# cerebro5_4.net
KiCad netlist of a schematic drawn in EAGLE
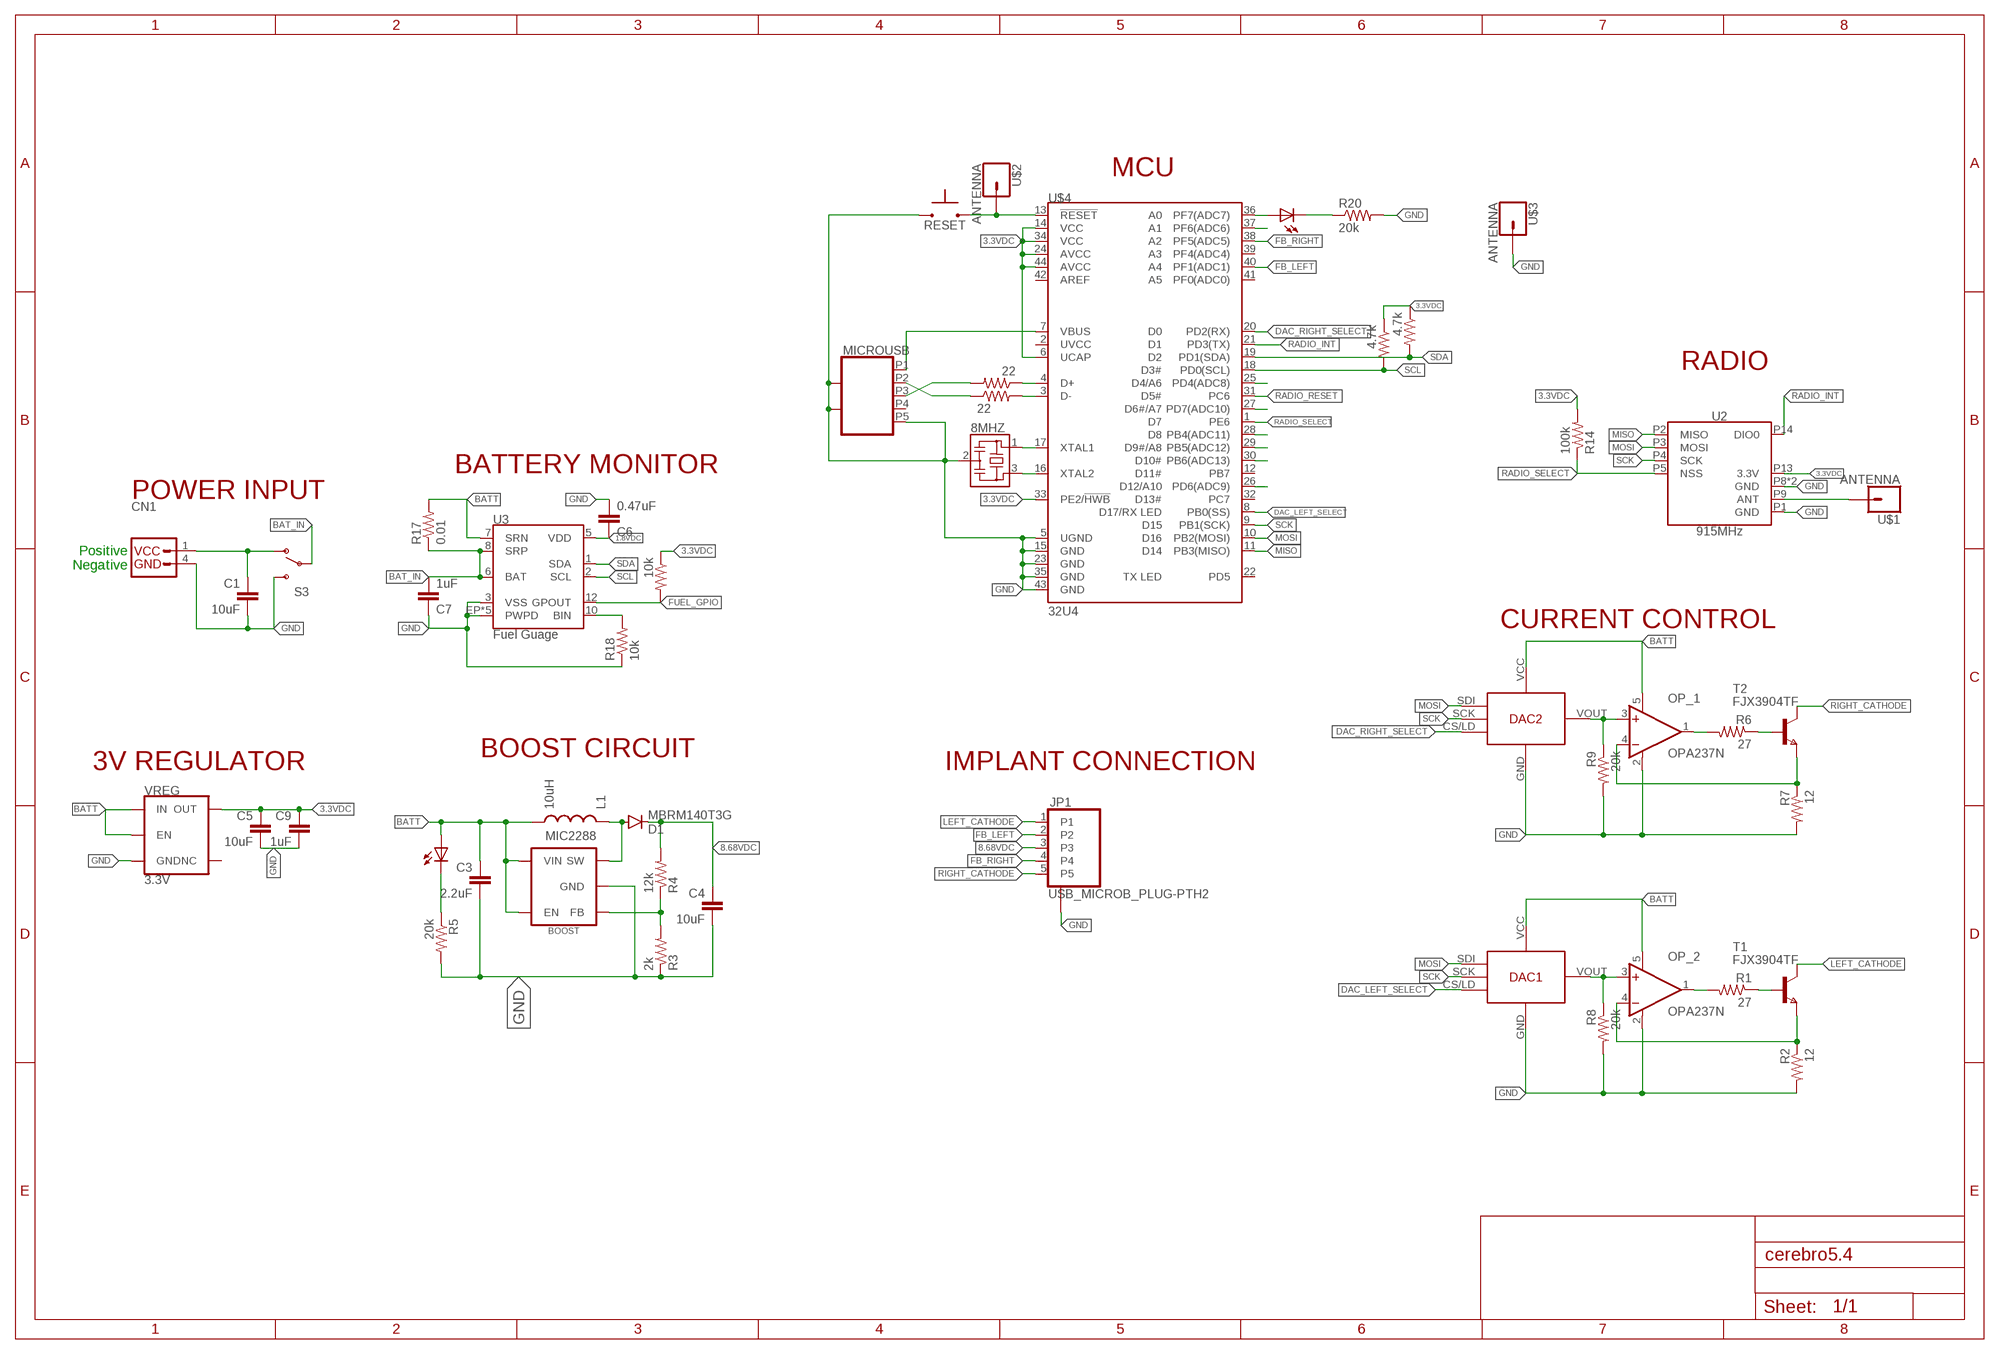
[diagram p0: schematic, sheet 1]

(export (version "E")
  (design (tool "Eeschema 10.0.6"))
  (components
    (comp (ref "8MHZ")
      (value "RESONATOR_CSTCE_V")
      (footprint "eagle-import:CSTCE_V")
      (libsource (lib "eagle-import") (part "RESONATOR_CSTCE_V"))
    )
    (comp (ref "C1")
      (value "10uF")
      (footprint "eagle-import:0805")
      (libsource (lib "eagle-import") (part "10UF-0805-10V-10%"))
    )
    (comp (ref "C3")
      (value "2.2uF")
      (footprint "eagle-import:0805")
      (libsource (lib "eagle-import") (part "2.2UF-0805-25V-(+80/-20%)"))
    )
    (comp (ref "C4")
      (value "10uF")
      (footprint "eagle-import:0805")
      (libsource (lib "eagle-import") (part "10UF-0805-10V-10%"))
    )
    (comp (ref "C5")
      (value "10uF")
      (footprint "eagle-import:0805")
      (libsource (lib "eagle-import") (part "10UF-0805-10V-10%"))
    )
    (comp (ref "C6")
      (value "0.47uF")
      (footprint "eagle-import:0805")
      (libsource (lib "eagle-import") (part "10UF-0805-10V-10%"))
    )
    (comp (ref "C7")
      (value "1uF")
      (footprint "eagle-import:0805")
      (libsource (lib "eagle-import") (part "10UF-0805-10V-10%"))
    )
    (comp (ref "C9")
      (value "1uF")
      (footprint "eagle-import:0805")
      (libsource (lib "eagle-import") (part "10UF-0805-10V-10%"))
    )
    (comp (ref "CN1")
      (value "JST-SRJS-1MM")
      (footprint "eagle-import:1X04_1MM_RA")
      (libsource (lib "eagle-import") (part "JST-SRJS-1MM"))
    )
    (comp (ref "D1")
      (value "MBRM140T3G")
      (footprint "eagle-import:POWERMITE")
      (libsource (lib "eagle-import") (part "DIODEPOWERMITE"))
    )
    (comp (ref "DAC1")
      (value "DAC_LTC2630")
      (footprint "eagle-import:SC-70")
      (libsource (lib "eagle-import") (part "DAC_LTC2630"))
    )
    (comp (ref "DAC2")
      (value "DAC_LTC2630")
      (footprint "eagle-import:SC-70")
      (libsource (lib "eagle-import") (part "DAC_LTC2630"))
    )
    (comp (ref "INDICATOR_LED")
      (value "RED")
      (footprint "eagle-import:CHIP-LED0603")
      (libsource (lib "eagle-import") (part "LEDCHIP-LED0603"))
    )
    (comp (ref "INDICATOR_LED1")
      (value "AMBER")
      (footprint "eagle-import:CHIP-LED0603")
      (libsource (lib "eagle-import") (part "LEDCHIP-LED0603"))
    )
    (comp (ref "JP1")
      (value "USB_MICROB_PLUG-PTH2")
      (footprint "eagle-import:MICRO-B-TH")
      (libsource (lib "eagle-import") (part "USB_MICROB_PLUG-PTH2"))
    )
    (comp (ref "L1")
      (value "10uH")
      (footprint "eagle-import:1812")
      (libsource (lib "eagle-import") (part "INDUCTORLQH4"))
    )
    (comp (ref "MIC2288")
      (value "BOOST")
      (footprint "eagle-import:SOT23-5")
      (libsource (lib "eagle-import") (part "BOOST_CONVERTER"))
    )
    (comp (ref "MICROUSB")
      (value "USB_MICRO_SOCKET_HORZ_REINFORCED")
      (footprint "eagle-import:USB_HORZ_REINFORCED_MICRO")
      (libsource (lib "eagle-import") (part "USB_MICRO_SOCKET_HORZ_REINFORCED"))
    )
    (comp (ref "OP_1")
      (value "OPA237N")
      (footprint "eagle-import:SOT23-5")
      (fields (field (name "MF") "TEXAS INSTRUMENTS") (field (name "MPN") "OPA237NA/250"))
      (libsource (lib "eagle-import") (part "OPA237N"))
    )
    (comp (ref "OP_2")
      (value "OPA237N")
      (footprint "eagle-import:SOT23-5")
      (fields (field (name "MF") "TEXAS INSTRUMENTS") (field (name "MPN") "OPA237NA/250"))
      (libsource (lib "eagle-import") (part "OPA237N"))
    )
    (comp (ref "R1")
      (value "27")
      (footprint "eagle-import:0603-RES")
      (libsource (lib "eagle-import") (part "RESISTOR0603-RES"))
    )
    (comp (ref "R2")
      (value "12")
      (footprint "eagle-import:0603-RES")
      (libsource (lib "eagle-import") (part "RESISTOR0603-RES"))
    )
    (comp (ref "R3")
      (value "2k")
      (footprint "eagle-import:0603-RES")
      (libsource (lib "eagle-import") (part "RESISTOR0603-RES"))
    )
    (comp (ref "R4")
      (value "12k")
      (footprint "eagle-import:0805")
      (libsource (lib "eagle-import") (part "RESISTOR0805-RES"))
    )
    (comp (ref "R5")
      (value "20k")
      (footprint "eagle-import:0603-RES")
      (libsource (lib "eagle-import") (part "RESISTOR0603-RES"))
    )
    (comp (ref "R6")
      (value "27")
      (footprint "eagle-import:0603-RES")
      (libsource (lib "eagle-import") (part "RESISTOR0603-RES"))
    )
    (comp (ref "R7")
      (value "12")
      (footprint "eagle-import:0603-RES")
      (libsource (lib "eagle-import") (part "RESISTOR0603-RES"))
    )
    (comp (ref "R8")
      (value "20k")
      (footprint "eagle-import:0603-RES")
      (libsource (lib "eagle-import") (part "RESISTOR0603-RES"))
    )
    (comp (ref "R9")
      (value "20k")
      (footprint "eagle-import:0603-RES")
      (libsource (lib "eagle-import") (part "RESISTOR0603-RES"))
    )
    (comp (ref "R12")
      (value "22")
      (footprint "eagle-import:0603-RES")
      (libsource (lib "eagle-import") (part "RESISTOR0603-RES"))
    )
    (comp (ref "R13")
      (value "22")
      (footprint "eagle-import:0603-RES")
      (libsource (lib "eagle-import") (part "RESISTOR0603-RES"))
    )
    (comp (ref "R14")
      (value "100k")
      (footprint "eagle-import:0603-RES")
      (libsource (lib "eagle-import") (part "RESISTOR0603-RES"))
    )
    (comp (ref "R15")
      (value "4.7k")
      (footprint "eagle-import:0603-RES")
      (libsource (lib "eagle-import") (part "RESISTOR0603-RES"))
    )
    (comp (ref "R16")
      (value "4.7k")
      (footprint "eagle-import:0603-RES")
      (libsource (lib "eagle-import") (part "RESISTOR0603-RES"))
    )
    (comp (ref "R17")
      (value "0.01")
      (footprint "eagle-import:1206")
      (libsource (lib "eagle-import") (part "RESISTOR1206"))
    )
    (comp (ref "R18")
      (value "10k")
      (footprint "eagle-import:0603-RES")
      (libsource (lib "eagle-import") (part "RESISTOR0603-RES"))
    )
    (comp (ref "R19")
      (value "10k")
      (footprint "eagle-import:0603-RES")
      (libsource (lib "eagle-import") (part "RESISTOR0603-RES"))
    )
    (comp (ref "R20")
      (value "20k")
      (footprint "eagle-import:0603-RES")
      (libsource (lib "eagle-import") (part "RESISTOR0603-RES"))
    )
    (comp (ref "RESET")
      (value "SWITCH-MOMENTARY-NO")
      (footprint "eagle-import:SWITCH_MOMENTARY_XS")
      (libsource (lib "eagle-import") (part "SWITCH-MOMENTARY-NO"))
    )
    (comp (ref "S3")
      (value "SWITCH-SPDTSMD2")
      (footprint "eagle-import:SWITCH-SPDT-SMD")
      (libsource (lib "eagle-import") (part "SWITCH-SPDTSMD2"))
    )
    (comp (ref "T1")
      (value "FJX3904TF")
      (footprint "eagle-import:SOT323")
      (fields (field (name "MPN") "DSS4160U-7"))
      (libsource (lib "eagle-import") (part "NPNSOT323"))
    )
    (comp (ref "T2")
      (value "FJX3904TF")
      (footprint "eagle-import:SOT323")
      (fields (field (name "MPN") "DSS4160U-7"))
      (libsource (lib "eagle-import") (part "NPNSOT323"))
    )
    (comp (ref "U$1")
      (value "ANTENNA")
      (footprint "eagle-import:1X01")
      (libsource (lib "eagle-import") (part "ANTENNA"))
    )
    (comp (ref "U$2")
      (value "ANTENNA")
      (footprint "eagle-import:1X01")
      (libsource (lib "eagle-import") (part "ANTENNA"))
    )
    (comp (ref "U$3")
      (value "ANTENNA")
      (footprint "eagle-import:1X01")
      (libsource (lib "eagle-import") (part "ANTENNA"))
    )
    (comp (ref "U$4")
      (value "32U4")
      (footprint "eagle-import:QFN-44-NOPAD")
      (libsource (lib "eagle-import") (part "ATMEGA32U4QFN2"))
    )
    (comp (ref "U2")
      (value "915MHz")
      (footprint "eagle-import:RFM69HCW-XXXS2")
      (libsource (lib "eagle-import") (part "RFM69HCW-915"))
    )
    (comp (ref "U3")
      (value "Fuel Guage")
      (footprint "eagle-import:PDSO-N12")
      (libsource (lib "eagle-import") (part "BQ27441-G1"))
    )
    (comp (ref "VREG")
      (value "3.3V")
      (footprint "eagle-import:SOT23-5")
      (libsource (lib "eagle-import") (part "V_REG_AP2112K-3.3V"))
    )
  )
  (nets
    (net (code "1") (name "1.8VDC") (class "Default")
      (node (ref "C6") (pin "1") (pinfunction "1_1") (pintype "passive"))
      (node (ref "U3") (pin "5") (pinfunction "VDD_5") (pintype "bidirectional"))
    )
    (net (code "2") (name "3.3VDC") (class "Default")
      (node (ref "C5") (pin "1") (pinfunction "1_1") (pintype "passive"))
      (node (ref "C9") (pin "1") (pinfunction "1_1") (pintype "passive"))
      (node (ref "R14") (pin "2") (pinfunction "2_2") (pintype "passive"))
      (node (ref "R15") (pin "1") (pinfunction "1_1") (pintype "passive"))
      (node (ref "R16") (pin "1") (pinfunction "1_1") (pintype "passive"))
      (node (ref "R19") (pin "1") (pinfunction "1_1") (pintype "passive"))
      (node (ref "U$4") (pin "14") (pinfunction "VCC_14") (pintype "bidirectional"))
      (node (ref "U$4") (pin "24") (pinfunction "AVCC_24") (pintype "bidirectional"))
      (node (ref "U$4") (pin "33") (pinfunction "PE2/~{HWB}_33") (pintype "bidirectional"))
      (node (ref "U$4") (pin "34") (pinfunction "VCC_34") (pintype "bidirectional"))
      (node (ref "U$4") (pin "44") (pinfunction "AVCC_44") (pintype "bidirectional"))
      (node (ref "U$4") (pin "6") (pinfunction "UCAP_6") (pintype "bidirectional"))
      (node (ref "U2") (pin "P13") (pinfunction "3.3V_P13") (pintype "power_in"))
      (node (ref "VREG") (pin "5") (pinfunction "OUT_5") (pintype "passive"))
    )
    (net (code "3") (name "8.68VDC") (class "Default")
      (node (ref "C4") (pin "1") (pinfunction "1_1") (pintype "passive"))
      (node (ref "D1") (pin "CATHODE") (pinfunction "C_CATHODE") (pintype "passive"))
      (node (ref "JP1") (pin "3") (pinfunction "P3_3") (pintype "bidirectional"))
      (node (ref "R4") (pin "2") (pinfunction "2_2") (pintype "passive"))
    )
    (net (code "4") (name "BATT") (class "Default")
      (node (ref "C3") (pin "1") (pinfunction "1_1") (pintype "passive"))
      (node (ref "DAC1") (pin "VCC") (pinfunction "VIN_VCC") (pintype "bidirectional"))
      (node (ref "DAC2") (pin "VCC") (pinfunction "VIN_VCC") (pintype "bidirectional"))
      (node (ref "INDICATOR_LED") (pin "A") (pinfunction "A_A") (pintype "passive"))
      (node (ref "L1") (pin "P$2") (pinfunction "2_P$2") (pintype "passive"))
      (node (ref "L1") (pin "P$4") (pinfunction "2_P$4") (pintype "passive"))
      (node (ref "MIC2288") (pin "4") (pinfunction "EN_4") (pintype "input"))
      (node (ref "MIC2288") (pin "5") (pinfunction "VIN_5") (pintype "passive"))
      (node (ref "OP_1") (pin "5") (pinfunction "V+_5") (pintype "power_in"))
      (node (ref "OP_2") (pin "5") (pinfunction "V+_5") (pintype "power_in"))
      (node (ref "R17") (pin "2") (pinfunction "2_2") (pintype "passive"))
      (node (ref "U3") (pin "7") (pinfunction "SRN_7") (pintype "bidirectional"))
      (node (ref "VREG") (pin "1") (pinfunction "IN_1") (pintype "input"))
      (node (ref "VREG") (pin "3") (pinfunction "EN_3") (pintype "input"))
    )
    (net (code "5") (name "BAT_IN") (class "Default")
      (node (ref "C7") (pin "2") (pinfunction "2_2") (pintype "passive"))
      (node (ref "R17") (pin "1") (pinfunction "1_1") (pintype "passive"))
      (node (ref "S3") (pin "2") (pinfunction "P_2") (pintype "passive"))
      (node (ref "U3") (pin "6") (pinfunction "BAT_6") (pintype "bidirectional"))
      (node (ref "U3") (pin "8") (pinfunction "SRP_8") (pintype "bidirectional"))
    )
    (net (code "6") (name "DAC_LEFT_SELECT") (class "Default")
      (node (ref "DAC1") (pin "CS/LD") (pinfunction "CS/LD_CS/LD") (pintype "bidirectional"))
      (node (ref "U$4") (pin "8") (pinfunction "PB0(SS)_8") (pintype "bidirectional"))
    )
    (net (code "7") (name "DAC_RIGHT_SELECT") (class "Default")
      (node (ref "DAC2") (pin "CS/LD") (pinfunction "CS/LD_CS/LD") (pintype "bidirectional"))
      (node (ref "U$4") (pin "20") (pinfunction "PD2(RX)_20") (pintype "bidirectional"))
    )
    (net (code "8") (name "FB_LEFT") (class "Default")
      (node (ref "JP1") (pin "2") (pinfunction "P2_2") (pintype "bidirectional"))
      (node (ref "U$4") (pin "40") (pinfunction "PF1(ADC1)_40") (pintype "bidirectional"))
    )
    (net (code "9") (name "FB_RIGHT") (class "Default")
      (node (ref "JP1") (pin "4") (pinfunction "P4_4") (pintype "bidirectional"))
      (node (ref "U$4") (pin "38") (pinfunction "PF5(ADC5)_38") (pintype "bidirectional"))
    )
    (net (code "10") (name "FUEL_GPIO") (class "Default")
      (node (ref "R19") (pin "2") (pinfunction "2_2") (pintype "passive"))
      (node (ref "U3") (pin "12") (pinfunction "GPOUT_12") (pintype "bidirectional"))
    )
    (net (code "11") (name "GND") (class "Default")
      (node (ref "8MHZ") (pin "2") (pinfunction "2_2") (pintype "passive"))
      (node (ref "C1") (pin "2") (pinfunction "2_2") (pintype "passive"))
      (node (ref "C3") (pin "2") (pinfunction "2_2") (pintype "passive"))
      (node (ref "C4") (pin "2") (pinfunction "2_2") (pintype "passive"))
      (node (ref "C5") (pin "2") (pinfunction "2_2") (pintype "passive"))
      (node (ref "C6") (pin "2") (pinfunction "2_2") (pintype "passive"))
      (node (ref "C7") (pin "1") (pinfunction "1_1") (pintype "passive"))
      (node (ref "C9") (pin "2") (pinfunction "2_2") (pintype "passive"))
      (node (ref "CN1") (pin "4") (pinfunction "1_4") (pintype "power_in"))
      (node (ref "DAC1") (pin "GND") (pinfunction "GND_GND") (pintype "bidirectional"))
      (node (ref "DAC2") (pin "GND") (pinfunction "GND_GND") (pintype "bidirectional"))
      (node (ref "JP1") (pin "P$1") (pinfunction "GND_PINS_P$1") (pintype "bidirectional"))
      (node (ref "JP1") (pin "P$2") (pinfunction "GND_PINS_P$2") (pintype "bidirectional"))
      (node (ref "MIC2288") (pin "2") (pinfunction "GND_2") (pintype "input"))
      (node (ref "MICROUSB") (pin "G1") (pinfunction "P$1_G1") (pintype "bidirectional"))
      (node (ref "MICROUSB") (pin "G2") (pinfunction "P$1_G2") (pintype "bidirectional"))
      (node (ref "MICROUSB") (pin "P$1") (pinfunction "P$2_P$1") (pintype "bidirectional"))
      (node (ref "MICROUSB") (pin "P$2") (pinfunction "P$2_P$2") (pintype "bidirectional"))
      (node (ref "MICROUSB") (pin "P5") (pinfunction "P5_P5") (pintype "bidirectional"))
      (node (ref "OP_1") (pin "2") (pinfunction "V-_2") (pintype "power_in"))
      (node (ref "OP_2") (pin "2") (pinfunction "V-_2") (pintype "power_in"))
      (node (ref "R18") (pin "1") (pinfunction "1_1") (pintype "passive"))
      (node (ref "R2") (pin "2") (pinfunction "2_2") (pintype "passive"))
      (node (ref "R20") (pin "2") (pinfunction "2_2") (pintype "passive"))
      (node (ref "R3") (pin "1") (pinfunction "1_1") (pintype "passive"))
      (node (ref "R5") (pin "2") (pinfunction "2_2") (pintype "passive"))
      (node (ref "R7") (pin "2") (pinfunction "2_2") (pintype "passive"))
      (node (ref "R8") (pin "2") (pinfunction "2_2") (pintype "passive"))
      (node (ref "R9") (pin "2") (pinfunction "2_2") (pintype "passive"))
      (node (ref "RESET") (pin "P$1") (pinfunction "1_P$1") (pintype "bidirectional"))
      (node (ref "S3") (pin "3") (pinfunction "S_3") (pintype "passive"))
      (node (ref "U$3") (pin "1") (pinfunction "1_1") (pintype "passive"))
      (node (ref "U$4") (pin "15") (pinfunction "GND_15") (pintype "bidirectional"))
      (node (ref "U$4") (pin "23") (pinfunction "GND_23") (pintype "bidirectional"))
      (node (ref "U$4") (pin "35") (pinfunction "GND_35") (pintype "bidirectional"))
      (node (ref "U$4") (pin "43") (pinfunction "GND_43") (pintype "bidirectional"))
      (node (ref "U$4") (pin "5") (pinfunction "UGND_5") (pintype "bidirectional"))
      (node (ref "U2") (pin "P1") (pinfunction "GND_P1") (pintype "power_in"))
      (node (ref "U2") (pin "P10") (pinfunction "GND_P10") (pintype "power_in"))
      (node (ref "U2") (pin "P8") (pinfunction "GND_P8") (pintype "power_in"))
      (node (ref "U3") (pin "3") (pinfunction "VSS_3") (pintype "bidirectional"))
      (node (ref "U3") (pin "EP") (pinfunction "PWPD_EP") (pintype "bidirectional"))
      (node (ref "U3") (pin "EP1") (pinfunction "PWPD_EP1") (pintype "bidirectional"))
      (node (ref "U3") (pin "EP2") (pinfunction "PWPD_EP2") (pintype "bidirectional"))
      (node (ref "U3") (pin "EP3") (pinfunction "PWPD_EP3") (pintype "bidirectional"))
      (node (ref "U3") (pin "EP4") (pinfunction "PWPD_EP4") (pintype "bidirectional"))
      (node (ref "VREG") (pin "2") (pinfunction "GND_2") (pintype "input"))
    )
    (net (code "12") (name "LEFT_CATHODE") (class "Default")
      (node (ref "JP1") (pin "1") (pinfunction "P1_1") (pintype "bidirectional"))
      (node (ref "T1") (pin "1") (pinfunction "C_1") (pintype "passive"))
    )
    (net (code "13") (name "MISO") (class "Default")
      (node (ref "U$4") (pin "11") (pinfunction "PB3(MISO)_11") (pintype "bidirectional"))
      (node (ref "U2") (pin "P2") (pinfunction "MISO_P2") (pintype "bidirectional"))
    )
    (net (code "14") (name "MOSI") (class "Default")
      (node (ref "DAC1") (pin "SDI") (pinfunction "SDI_SDI") (pintype "bidirectional"))
      (node (ref "DAC2") (pin "SDI") (pinfunction "SDI_SDI") (pintype "bidirectional"))
      (node (ref "U$4") (pin "10") (pinfunction "PB2(MOSI)_10") (pintype "bidirectional"))
      (node (ref "U2") (pin "P3") (pinfunction "MOSI_P3") (pintype "input"))
    )
    (net (code "15") (name "Net-(CN1-2)") (class "Default")
      (node (ref "C1") (pin "1") (pinfunction "1_1") (pintype "passive"))
      (node (ref "CN1") (pin "1") (pinfunction "2_1") (pintype "power_in"))
      (node (ref "S3") (pin "1") (pinfunction "O_1") (pintype "passive"))
    )
    (net (code "16") (name "Net-(D1-A)") (class "Default")
      (node (ref "D1") (pin "ANODE") (pinfunction "A_ANODE") (pintype "passive"))
      (node (ref "L1") (pin "P$1") (pinfunction "1_P$1") (pintype "passive"))
      (node (ref "L1") (pin "P$3") (pinfunction "1_P$3") (pintype "passive"))
      (node (ref "MIC2288") (pin "1") (pinfunction "SW_1") (pintype "input"))
    )
    (net (code "17") (name "Net-(INDICATOR_LED-PadC)") (class "Default")
      (node (ref "INDICATOR_LED") (pin "C") (pinfunction "C_C") (pintype "passive"))
      (node (ref "R5") (pin "1") (pinfunction "1_1") (pintype "passive"))
    )
    (net (code "18") (name "Net-(INDICATOR_LED1-PadC)") (class "Default")
      (node (ref "INDICATOR_LED1") (pin "C") (pinfunction "C_C") (pintype "passive"))
      (node (ref "R20") (pin "1") (pinfunction "1_1") (pintype "passive"))
    )
    (net (code "19") (name "Net-(MIC2288-FB)") (class "Default")
      (node (ref "MIC2288") (pin "3") (pinfunction "FB_3") (pintype "input"))
      (node (ref "R3") (pin "2") (pinfunction "2_2") (pintype "passive"))
      (node (ref "R4") (pin "1") (pinfunction "1_1") (pintype "passive"))
    )
    (net (code "20") (name "Net-(MICROUSB-PadP2)") (class "Default")
      (node (ref "MICROUSB") (pin "P2") (pinfunction "P2_P2") (pintype "bidirectional"))
      (node (ref "R13") (pin "1") (pinfunction "1_1") (pintype "passive"))
    )
    (net (code "21") (name "Net-(MICROUSB-PadP3)") (class "Default")
      (node (ref "MICROUSB") (pin "P3") (pinfunction "P3_P3") (pintype "bidirectional"))
      (node (ref "R12") (pin "2") (pinfunction "2_2") (pintype "passive"))
    )
    (net (code "22") (name "Net-(OP_1-+IN)") (class "Default")
      (node (ref "DAC2") (pin "VOUT") (pinfunction "VOUT_VOUT") (pintype "bidirectional"))
      (node (ref "OP_1") (pin "3") (pinfunction "+IN_3") (pintype "input"))
      (node (ref "R9") (pin "1") (pinfunction "1_1") (pintype "passive"))
    )
    (net (code "23") (name "Net-(OP_1--IN)") (class "Default")
      (node (ref "OP_1") (pin "4") (pinfunction "-IN_4") (pintype "input"))
      (node (ref "R7") (pin "1") (pinfunction "1_1") (pintype "passive"))
      (node (ref "T2") (pin "3") (pinfunction "E_3") (pintype "passive"))
    )
    (net (code "24") (name "Net-(OP_1-OUT)") (class "Default")
      (node (ref "OP_1") (pin "1") (pinfunction "OUT_1") (pintype "output"))
      (node (ref "R6") (pin "2") (pinfunction "2_2") (pintype "passive"))
    )
    (net (code "25") (name "Net-(OP_2-+IN)") (class "Default")
      (node (ref "DAC1") (pin "VOUT") (pinfunction "VOUT_VOUT") (pintype "bidirectional"))
      (node (ref "OP_2") (pin "3") (pinfunction "+IN_3") (pintype "input"))
      (node (ref "R8") (pin "1") (pinfunction "1_1") (pintype "passive"))
    )
    (net (code "26") (name "Net-(OP_2--IN)") (class "Default")
      (node (ref "OP_2") (pin "4") (pinfunction "-IN_4") (pintype "input"))
      (node (ref "R2") (pin "1") (pinfunction "1_1") (pintype "passive"))
      (node (ref "T1") (pin "3") (pinfunction "E_3") (pintype "passive"))
    )
    (net (code "27") (name "Net-(OP_2-OUT)") (class "Default")
      (node (ref "OP_2") (pin "1") (pinfunction "OUT_1") (pintype "output"))
      (node (ref "R1") (pin "2") (pinfunction "2_2") (pintype "passive"))
    )
    (net (code "28") (name "Net-(RESET-2)") (class "Default")
      (node (ref "RESET") (pin "P$2") (pinfunction "2_P$2") (pintype "bidirectional"))
      (node (ref "U$2") (pin "1") (pinfunction "1_1") (pintype "passive"))
      (node (ref "U$4") (pin "13") (pinfunction "~{RESET}_13") (pintype "bidirectional"))
    )
    (net (code "29") (name "Net-(T1-B)") (class "Default")
      (node (ref "R1") (pin "1") (pinfunction "1_1") (pintype "passive"))
      (node (ref "T1") (pin "2") (pinfunction "B_2") (pintype "passive"))
    )
    (net (code "30") (name "Net-(T2-B)") (class "Default")
      (node (ref "R6") (pin "1") (pinfunction "1_1") (pintype "passive"))
      (node (ref "T2") (pin "2") (pinfunction "B_2") (pintype "passive"))
    )
    (net (code "31") (name "Net-(U$4-D+)") (class "Default")
      (node (ref "R12") (pin "1") (pinfunction "1_1") (pintype "passive"))
      (node (ref "U$4") (pin "4") (pinfunction "D+_4") (pintype "bidirectional"))
    )
    (net (code "32") (name "Net-(U$4-D-)") (class "Default")
      (node (ref "R13") (pin "2") (pinfunction "2_2") (pintype "passive"))
      (node (ref "U$4") (pin "3") (pinfunction "D-_3") (pintype "bidirectional"))
    )
    (net (code "33") (name "Net-(U$4-PF7(ADC7))") (class "Default")
      (node (ref "INDICATOR_LED1") (pin "A") (pinfunction "A_A") (pintype "passive"))
      (node (ref "U$4") (pin "36") (pinfunction "PF7(ADC7)_36") (pintype "bidirectional"))
    )
    (net (code "34") (name "Net-(U$4-VBUS)") (class "Default")
      (node (ref "MICROUSB") (pin "P1") (pinfunction "P1_P1") (pintype "bidirectional"))
      (node (ref "U$4") (pin "7") (pinfunction "VBUS_7") (pintype "bidirectional"))
    )
    (net (code "35") (name "Net-(U$4-XTAL1)") (class "Default")
      (node (ref "8MHZ") (pin "1") (pinfunction "1_1") (pintype "passive"))
      (node (ref "U$4") (pin "17") (pinfunction "XTAL1_17") (pintype "bidirectional"))
    )
    (net (code "36") (name "Net-(U$4-XTAL2)") (class "Default")
      (node (ref "8MHZ") (pin "3") (pinfunction "3_3") (pintype "passive"))
      (node (ref "U$4") (pin "16") (pinfunction "XTAL2_16") (pintype "bidirectional"))
    )
    (net (code "37") (name "Net-(U2-ANT)") (class "Default")
      (node (ref "U$1") (pin "1") (pinfunction "1_1") (pintype "passive"))
      (node (ref "U2") (pin "P9") (pinfunction "ANT_P9") (pintype "passive"))
    )
    (net (code "38") (name "Net-(U3-BIN)") (class "Default")
      (node (ref "R18") (pin "2") (pinfunction "2_2") (pintype "passive"))
      (node (ref "U3") (pin "10") (pinfunction "BIN_10") (pintype "bidirectional"))
    )
    (net (code "39") (name "RADIO_INT") (class "Default")
      (node (ref "U$4") (pin "21") (pinfunction "PD3(TX)_21") (pintype "bidirectional"))
      (node (ref "U2") (pin "P14") (pinfunction "DIO0_P14") (pintype "bidirectional"))
    )
    (net (code "40") (name "RADIO_RESET") (class "Default")
      (node (ref "U$4") (pin "31") (pinfunction "PC6_31") (pintype "bidirectional"))
    )
    (net (code "41") (name "RADIO_SELECT") (class "Default")
      (node (ref "R14") (pin "1") (pinfunction "1_1") (pintype "passive"))
      (node (ref "U$4") (pin "1") (pinfunction "PE6_1") (pintype "bidirectional"))
      (node (ref "U2") (pin "P5") (pinfunction "NSS_P5") (pintype "input"))
    )
    (net (code "42") (name "RIGHT_CATHODE") (class "Default")
      (node (ref "JP1") (pin "5") (pinfunction "P5_5") (pintype "bidirectional"))
      (node (ref "T2") (pin "1") (pinfunction "C_1") (pintype "passive"))
    )
    (net (code "43") (name "SCK") (class "Default")
      (node (ref "DAC1") (pin "SCK") (pinfunction "SCK_SCK") (pintype "bidirectional"))
      (node (ref "DAC2") (pin "SCK") (pinfunction "SCK_SCK") (pintype "bidirectional"))
      (node (ref "U$4") (pin "9") (pinfunction "PB1(SCK)_9") (pintype "bidirectional"))
      (node (ref "U2") (pin "P4") (pinfunction "SCK_P4") (pintype "input"))
    )
    (net (code "44") (name "SCL") (class "Default")
      (node (ref "R15") (pin "2") (pinfunction "2_2") (pintype "passive"))
      (node (ref "U$4") (pin "18") (pinfunction "PD0(SCL)_18") (pintype "bidirectional"))
      (node (ref "U3") (pin "2") (pinfunction "SCL_2") (pintype "bidirectional"))
    )
    (net (code "45") (name "SDA") (class "Default")
      (node (ref "R16") (pin "2") (pinfunction "2_2") (pintype "passive"))
      (node (ref "U$4") (pin "19") (pinfunction "PD1(SDA)_19") (pintype "bidirectional"))
      (node (ref "U3") (pin "1") (pinfunction "SDA_1") (pintype "bidirectional"))
    )
    (net (code "46") (name "unconnected-(MICROUSB-PadP4)") (class "Default")
      (node (ref "MICROUSB") (pin "P4") (pinfunction "P4_P4") (pintype "bidirectional"))
    )
    (net (code "47") (name "unconnected-(U$4-AREF-Pad42)") (class "Default")
      (node (ref "U$4") (pin "42") (pinfunction "AREF_42") (pintype "bidirectional"))
    )
    (net (code "48") (name "unconnected-(U$4-PB4(ADC11)-Pad28)") (class "Default")
      (node (ref "U$4") (pin "28") (pinfunction "PB4(ADC11)_28") (pintype "bidirectional"))
    )
    (net (code "49") (name "unconnected-(U$4-PB5(ADC12)-Pad29)") (class "Default")
      (node (ref "U$4") (pin "29") (pinfunction "PB5(ADC12)_29") (pintype "bidirectional"))
    )
    (net (code "50") (name "unconnected-(U$4-PB6(ADC13)-Pad30)") (class "Default")
      (node (ref "U$4") (pin "30") (pinfunction "PB6(ADC13)_30") (pintype "bidirectional"))
    )
    (net (code "51") (name "unconnected-(U$4-PB7-Pad12)") (class "Default")
      (node (ref "U$4") (pin "12") (pinfunction "PB7_12") (pintype "bidirectional"))
    )
    (net (code "52") (name "unconnected-(U$4-PC7-Pad32)") (class "Default")
      (node (ref "U$4") (pin "32") (pinfunction "PC7_32") (pintype "bidirectional"))
    )
    (net (code "53") (name "unconnected-(U$4-PD4(ADC8)-Pad25)") (class "Default")
      (node (ref "U$4") (pin "25") (pinfunction "PD4(ADC8)_25") (pintype "bidirectional"))
    )
    (net (code "54") (name "unconnected-(U$4-PD5-Pad22)") (class "Default")
      (node (ref "U$4") (pin "22") (pinfunction "PD5_22") (pintype "bidirectional"))
    )
    (net (code "55") (name "unconnected-(U$4-PD6(ADC9)-Pad26)") (class "Default")
      (node (ref "U$4") (pin "26") (pinfunction "PD6(ADC9)_26") (pintype "bidirectional"))
    )
    (net (code "56") (name "unconnected-(U$4-PD7(ADC10)-Pad27)") (class "Default")
      (node (ref "U$4") (pin "27") (pinfunction "PD7(ADC10)_27") (pintype "bidirectional"))
    )
    (net (code "57") (name "unconnected-(U$4-PF0(ADC0)-Pad41)") (class "Default")
      (node (ref "U$4") (pin "41") (pinfunction "PF0(ADC0)_41") (pintype "bidirectional"))
    )
    (net (code "58") (name "unconnected-(U$4-PF4(ADC4)-Pad39)") (class "Default")
      (node (ref "U$4") (pin "39") (pinfunction "PF4(ADC4)_39") (pintype "bidirectional"))
    )
    (net (code "59") (name "unconnected-(U$4-PF6(ADC6)-Pad37)") (class "Default")
      (node (ref "U$4") (pin "37") (pinfunction "PF6(ADC6)_37") (pintype "bidirectional"))
    )
    (net (code "60") (name "unconnected-(U$4-UVCC-Pad2)") (class "Default")
      (node (ref "U$4") (pin "2") (pinfunction "UVCC_2") (pintype "bidirectional"))
    )
    (net (code "61") (name "unconnected-(VREG-NC-Pad4)") (class "Default")
      (node (ref "VREG") (pin "4") (pinfunction "NC_4") (pintype "no_connect"))
    )
  )
)
